# CONVEYOR-v2_0.net
KiCad netlist of a schematic drawn in EAGLE
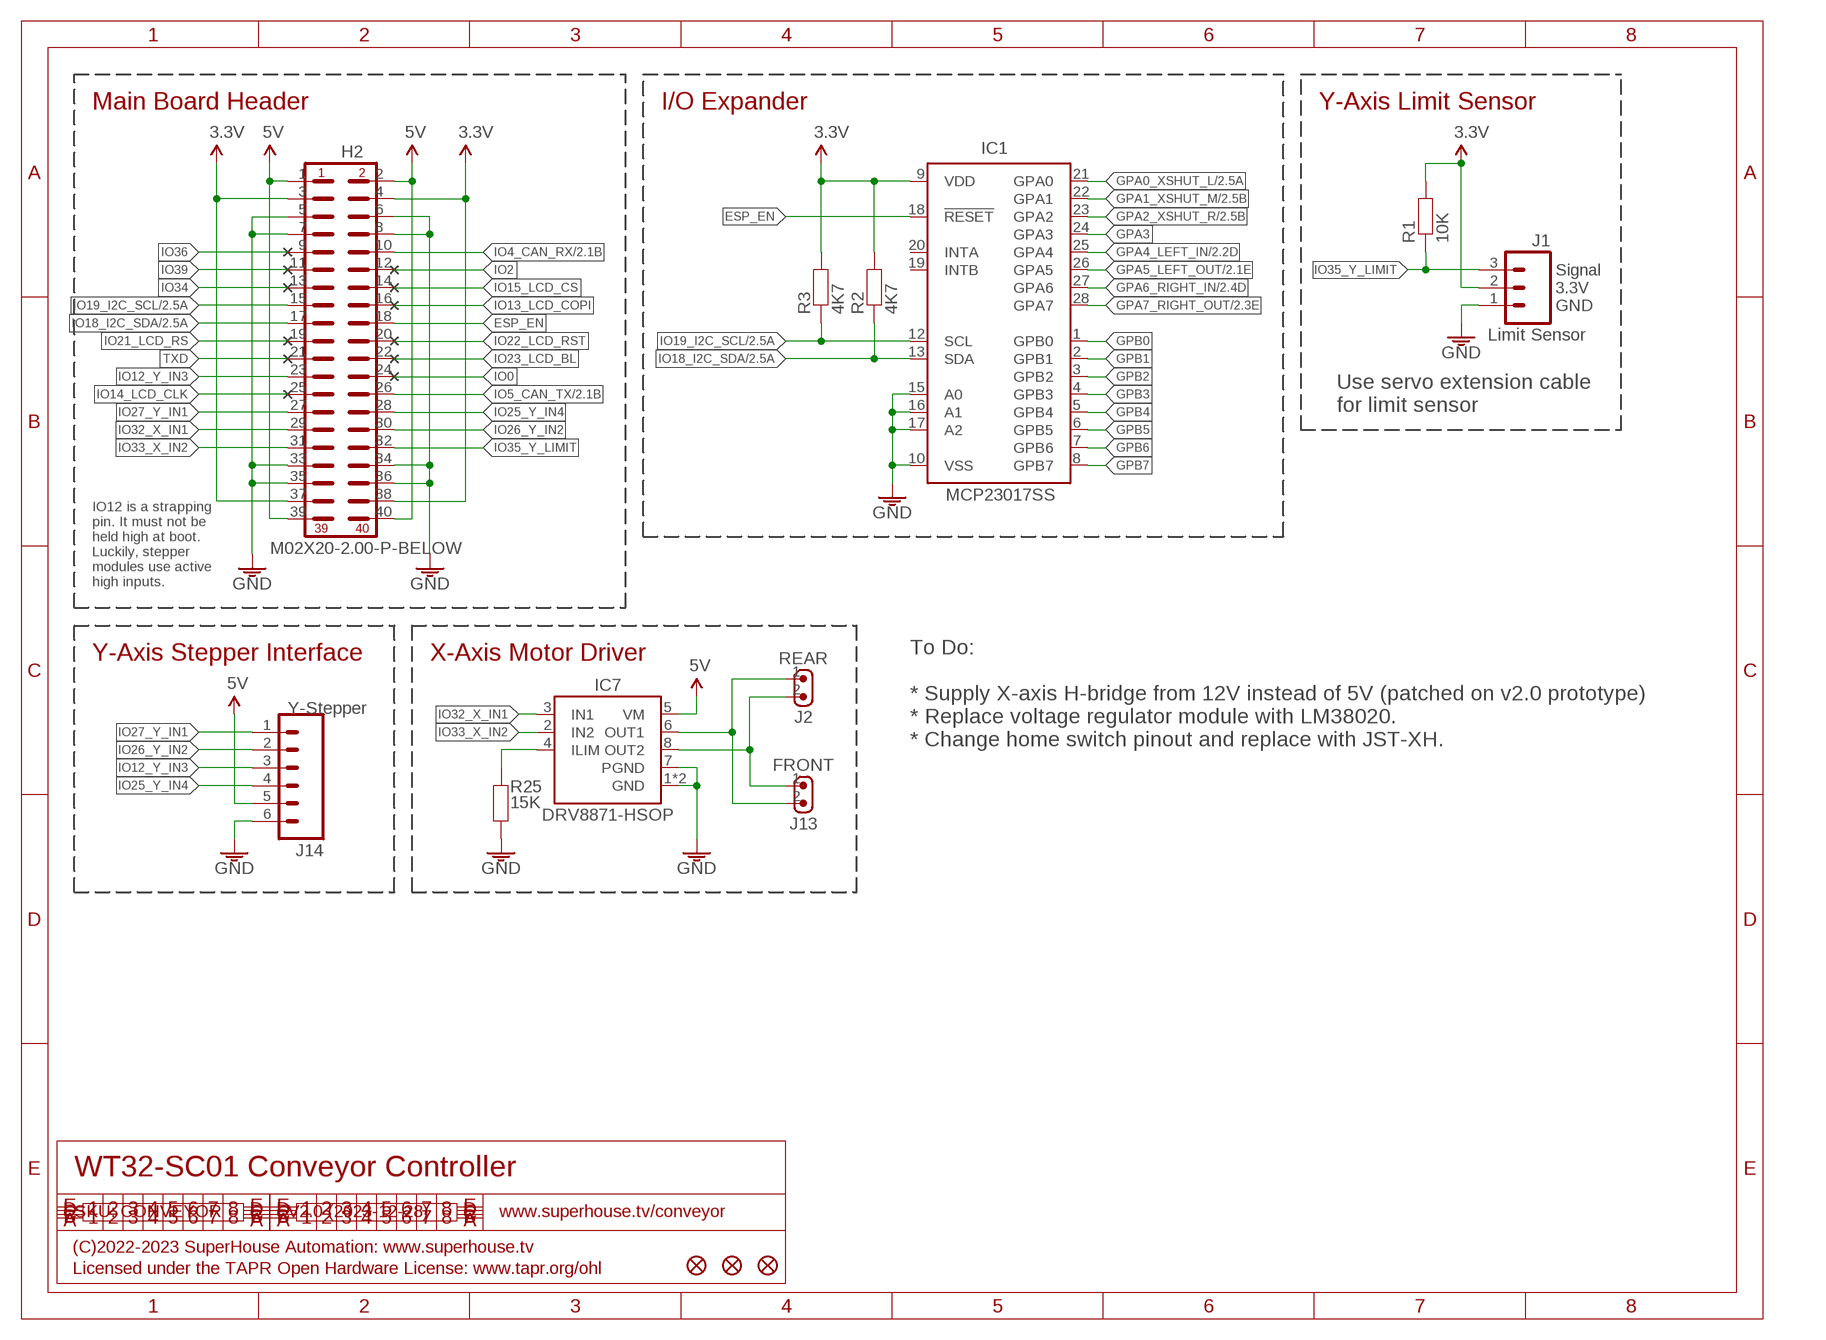
[diagram p0: schematic, sheet 1]
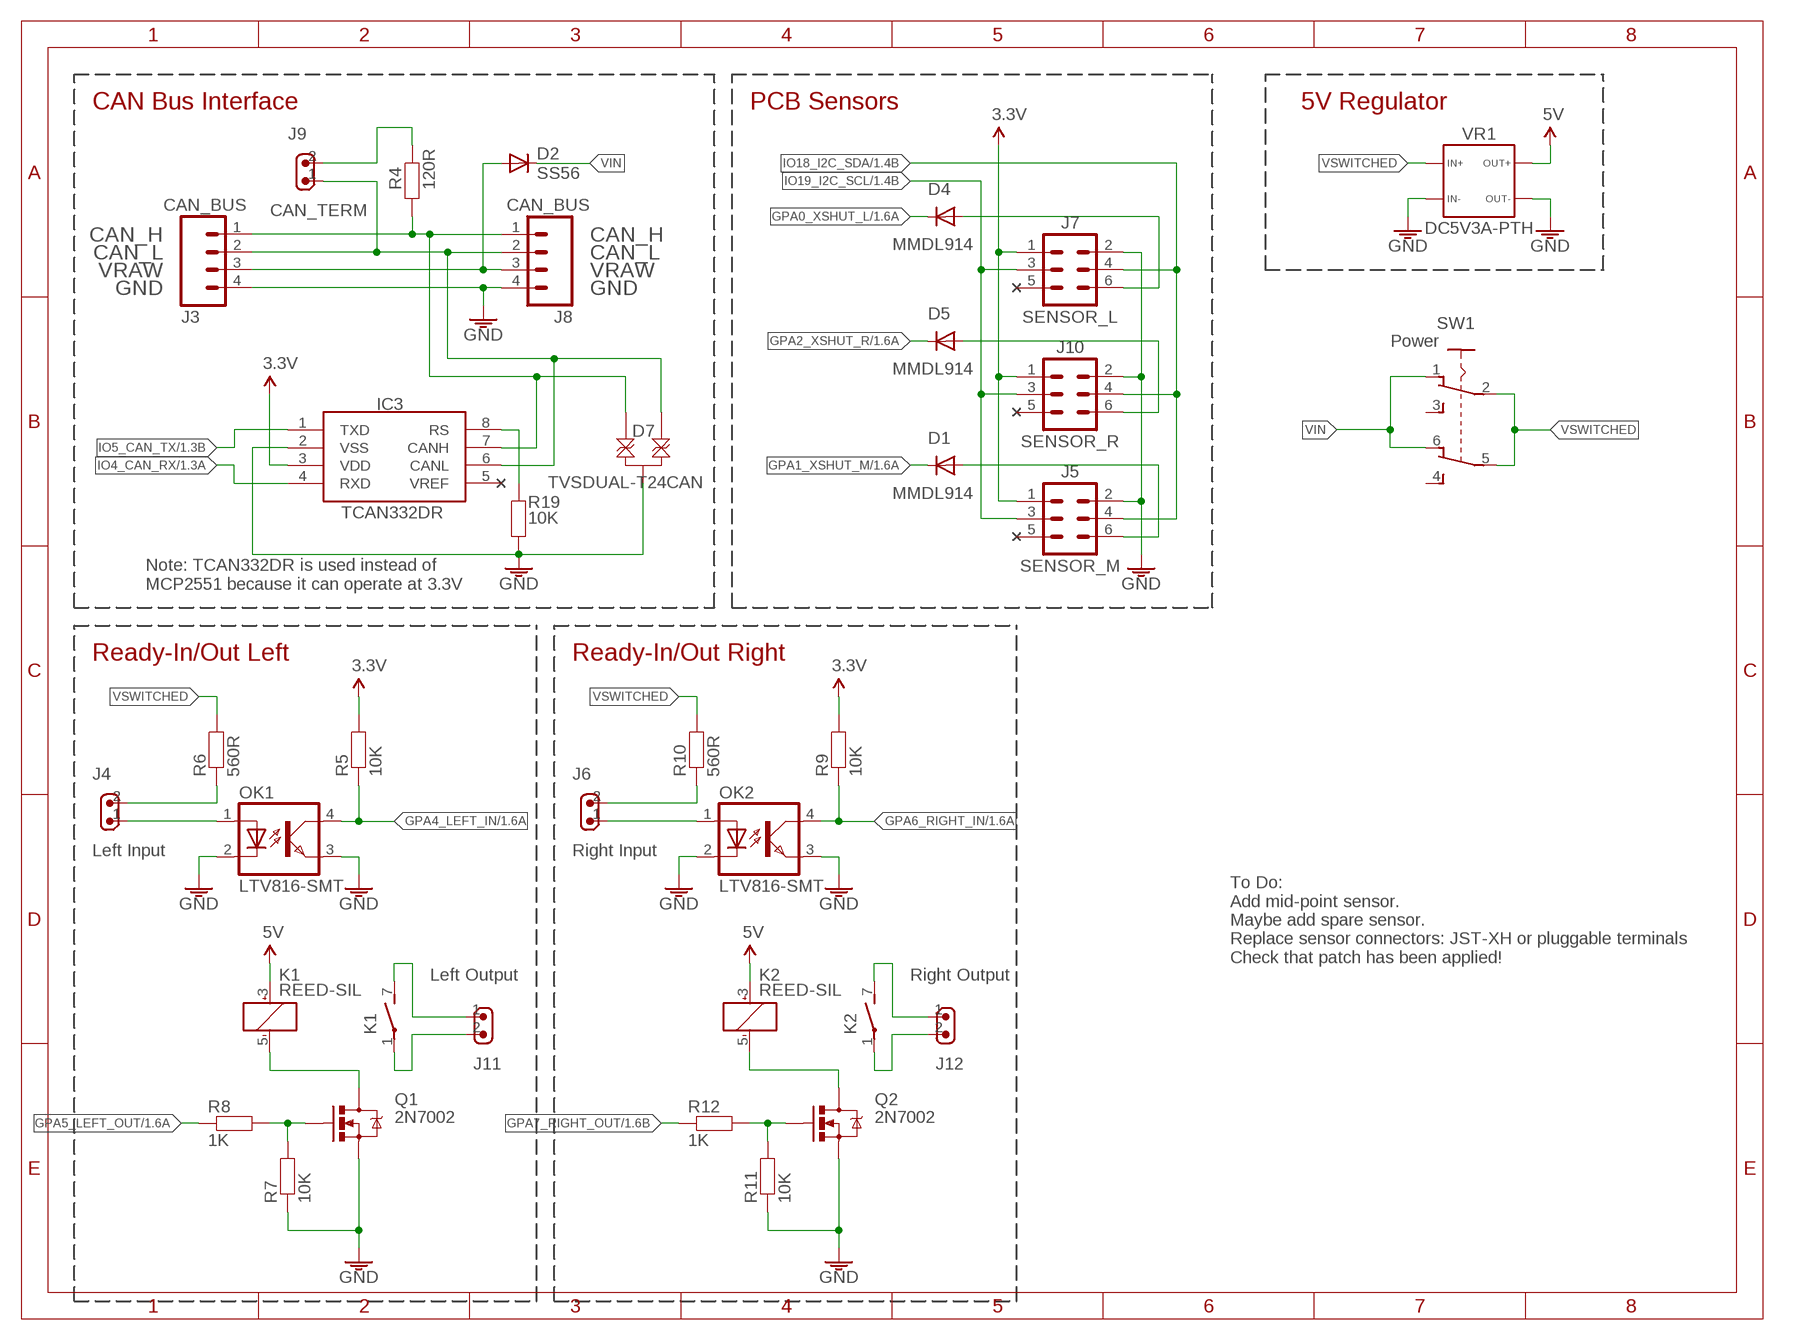
[diagram p1: schematic, sheet 2]

(export (version "E")
  (design (tool "Eeschema 10.0.6"))
  (components
    (comp (ref "D1")
      (value "MMDL914")
      (footprint "eagle-import:SOD-323")
      (libsource (lib "eagle-import") (part "DIODESOD"))
    )
    (comp (ref "D2")
      (value "SS56")
      (footprint "eagle-import:SMA-DIODE")
      (libsource (lib "eagle-import") (part "DIODESMA"))
    )
    (comp (ref "D4")
      (value "MMDL914")
      (footprint "eagle-import:SOD-323")
      (libsource (lib "eagle-import") (part "DIODESOD"))
    )
    (comp (ref "D5")
      (value "MMDL914")
      (footprint "eagle-import:SOD-323")
      (libsource (lib "eagle-import") (part "DIODESOD"))
    )
    (comp (ref "D7")
      (value "TVSDUAL-T24CAN")
      (footprint "eagle-import:SOT23-3")
      (libsource (lib "eagle-import") (part "TVSDUAL-T24CAN"))
    )
    (comp (ref "IC3")
      (value "TCAN332DR")
      (footprint "eagle-import:SO08")
      (libsource (lib "eagle-import") (part "MCP2551"))
    )
    (comp (ref "J3")
      (value "CAN_BUS")
      (footprint "eagle-import:SCREWTERMINAL-3.81MM-VERT-4")
      (libsource (lib "eagle-import") (part "M04-SCREW-3.81MM-VERT-PLUG"))
    )
    (comp (ref "J4")
      (value "Left Input")
      (footprint "eagle-import:1X02-KF2510")
      (libsource (lib "eagle-import") (part "M02-KF2510"))
    )
    (comp (ref "J5")
      (value "SENSOR_M")
      (footprint "eagle-import:2X3-2.54-SHROUDED")
      (libsource (lib "eagle-import") (part "M02X3-SHROUDED"))
    )
    (comp (ref "J6")
      (value "Right Input")
      (footprint "eagle-import:1X02-KF2510")
      (libsource (lib "eagle-import") (part "M02-KF2510"))
    )
    (comp (ref "J7")
      (value "SENSOR_L")
      (footprint "eagle-import:2X3-2.54-SHROUDED")
      (libsource (lib "eagle-import") (part "M02X3-SHROUDED"))
    )
    (comp (ref "J8")
      (value "CAN_BUS")
      (footprint "eagle-import:SCREWTERMINAL-3.81MM-VERT-4")
      (libsource (lib "eagle-import") (part "M04-SCREW-3.81MM-VERT-PLUG"))
    )
    (comp (ref "J9")
      (value "CAN_TERM")
      (footprint "eagle-import:1X02-P-JUMP-Y")
      (libsource (lib "eagle-import") (part "M02-PIN-JUMP-Y"))
    )
    (comp (ref "J10")
      (value "SENSOR_R")
      (footprint "eagle-import:2X3-2.54-SHROUDED")
      (libsource (lib "eagle-import") (part "M02X3-SHROUDED"))
    )
    (comp (ref "J11")
      (value "Left Output")
      (footprint "eagle-import:1X02-KF2510")
      (libsource (lib "eagle-import") (part "M02-KF2510"))
    )
    (comp (ref "J12")
      (value "Right Output")
      (footprint "eagle-import:1X02-KF2510")
      (libsource (lib "eagle-import") (part "M02-KF2510"))
    )
    (comp (ref "K1")
      (value "REED-SIL")
      (footprint "eagle-import:REED")
      (libsource (lib "eagle-import") (part "REED-SIL"))
    )
    (comp (ref "K2")
      (value "REED-SIL")
      (footprint "eagle-import:REED")
      (libsource (lib "eagle-import") (part "REED-SIL"))
    )
    (comp (ref "OK1")
      (value "LTV816-SMT")
      (footprint "eagle-import:SMD4")
      (libsource (lib "eagle-import") (part "LTV816-SMT"))
    )
    (comp (ref "OK2")
      (value "LTV816-SMT")
      (footprint "eagle-import:SMD4")
      (libsource (lib "eagle-import") (part "LTV816-SMT"))
    )
    (comp (ref "Q1")
      (value "2N7002")
      (footprint "eagle-import:SOT23-3")
      (libsource (lib "eagle-import") (part "MOSFET-NCHANNEL-233"))
    )
    (comp (ref "Q2")
      (value "2N7002")
      (footprint "eagle-import:SOT23-3")
      (libsource (lib "eagle-import") (part "MOSFET-NCHANNEL-233"))
    )
    (comp (ref "R4")
      (value "120R")
      (footprint "eagle-import:R2010")
      (libsource (lib "eagle-import") (part "RESISTOR2010"))
    )
    (comp (ref "R5")
      (value "10K")
      (footprint "eagle-import:R0603")
      (libsource (lib "eagle-import") (part "RESISTOR0603"))
    )
    (comp (ref "R6")
      (value "560R")
      (footprint "eagle-import:R0603")
      (libsource (lib "eagle-import") (part "RESISTOR0603"))
    )
    (comp (ref "R7")
      (value "10K")
      (footprint "eagle-import:R0603")
      (libsource (lib "eagle-import") (part "RESISTOR0603"))
    )
    (comp (ref "R8")
      (value "1K")
      (footprint "eagle-import:R0603")
      (libsource (lib "eagle-import") (part "RESISTOR0603"))
    )
    (comp (ref "R9")
      (value "10K")
      (footprint "eagle-import:R0603")
      (libsource (lib "eagle-import") (part "RESISTOR0603"))
    )
    (comp (ref "R10")
      (value "560R")
      (footprint "eagle-import:R0603")
      (libsource (lib "eagle-import") (part "RESISTOR0603"))
    )
    (comp (ref "R11")
      (value "10K")
      (footprint "eagle-import:R0603")
      (libsource (lib "eagle-import") (part "RESISTOR0603"))
    )
    (comp (ref "R12")
      (value "1K")
      (footprint "eagle-import:R0603")
      (libsource (lib "eagle-import") (part "RESISTOR0603"))
    )
    (comp (ref "R19")
      (value "10K")
      (footprint "eagle-import:R0603")
      (libsource (lib "eagle-import") (part "RESISTOR0603"))
    )
    (comp (ref "SW1")
      (value "Power")
      (footprint "eagle-import:7201SD9AV2BE")
      (libsource (lib "eagle-import") (part "SWITCH-DPDT3"))
    )
    (comp (ref "VR1")
      (value "DC5V3A-PTH")
      (footprint "eagle-import:DC5V3A-PTH")
      (libsource (lib "eagle-import") (part "DC5V3A-PTH"))
    )
    (comp (ref "H2")
      (value "M02X20-2.00-P-BELOW")
      (footprint "eagle-import:2X20-2.00-P-BELOW")
      (libsource (lib "eagle-import") (part "M02X20-2.00-P-BELOW"))
    )
    (comp (ref "IC1")
      (value "MCP23017SS")
      (footprint "eagle-import:SSOP28")
      (libsource (lib "eagle-import") (part "MCP23017SS"))
    )
    (comp (ref "IC7")
      (value "DRV8871-HSOP")
      (footprint "eagle-import:SOIC8T")
      (libsource (lib "eagle-import") (part "DRV8871-HSOP"))
    )
    (comp (ref "J1")
      (value "Limit Sensor")
      (footprint "eagle-import:1X03-P")
      (libsource (lib "eagle-import") (part "M03-PIN"))
    )
    (comp (ref "J2")
      (value "REAR")
      (footprint "eagle-import:JST-B2B-XH-A")
      (libsource (lib "eagle-import") (part "M02-B2B-XH"))
    )
    (comp (ref "J13")
      (value "FRONT")
      (footprint "eagle-import:JST-B2B-XH-A")
      (libsource (lib "eagle-import") (part "M02-B2B-XH"))
    )
    (comp (ref "J14")
      (value "Y-Stepper")
      (footprint "eagle-import:JST-B6B-XH-A")
      (libsource (lib "eagle-import") (part "M06-B6B-XH"))
    )
    (comp (ref "R1")
      (value "10K")
      (footprint "eagle-import:R0603")
      (libsource (lib "eagle-import") (part "RESISTOR0603"))
    )
    (comp (ref "R2")
      (value "4K7")
      (footprint "eagle-import:R0603")
      (libsource (lib "eagle-import") (part "RESISTOR0603"))
    )
    (comp (ref "R3")
      (value "4K7")
      (footprint "eagle-import:R0603")
      (libsource (lib "eagle-import") (part "RESISTOR0603"))
    )
    (comp (ref "R25")
      (value "15K")
      (footprint "eagle-import:R0603")
      (libsource (lib "eagle-import") (part "RESISTOR0603"))
    )
    (comp (ref "U$4")
      (value "FIDUCIAL1X2.5")
      (footprint "eagle-import:FIDUCIAL-1X2.5")
      (libsource (lib "eagle-import") (part "FIDUCIAL1X2.5"))
    )
    (comp (ref "U$5")
      (value "FIDUCIAL1X2.5")
      (footprint "eagle-import:FIDUCIAL-1X2.5")
      (libsource (lib "eagle-import") (part "FIDUCIAL1X2.5"))
    )
    (comp (ref "U$6")
      (value "FIDUCIAL1X2.5")
      (footprint "eagle-import:FIDUCIAL-1X2.5")
      (libsource (lib "eagle-import") (part "FIDUCIAL1X2.5"))
    )
  )
  (nets
    (net (code "1") (name "3.3V") (class "Default")
      (node (ref "H2") (pin "3") (pinfunction "3_3") (pintype "passive"))
      (node (ref "H2") (pin "37") (pinfunction "37_37") (pintype "passive"))
      (node (ref "H2") (pin "38") (pinfunction "38_38") (pintype "passive"))
      (node (ref "H2") (pin "4") (pinfunction "4_4") (pintype "passive"))
      (node (ref "IC1") (pin "9") (pinfunction "VDD_9") (pintype "power_in"))
      (node (ref "IC3") (pin "3") (pinfunction "VDD_3") (pintype "bidirectional"))
      (node (ref "J1") (pin "2") (pinfunction "2_2") (pintype "passive"))
      (node (ref "J10") (pin "1") (pinfunction "1_1") (pintype "passive"))
      (node (ref "J5") (pin "1") (pinfunction "1_1") (pintype "passive"))
      (node (ref "J7") (pin "1") (pinfunction "1_1") (pintype "passive"))
      (node (ref "R1") (pin "2") (pinfunction "2_2") (pintype "passive"))
      (node (ref "R2") (pin "2") (pinfunction "2_2") (pintype "passive"))
      (node (ref "R3") (pin "2") (pinfunction "2_2") (pintype "passive"))
      (node (ref "R5") (pin "2") (pinfunction "2_2") (pintype "passive"))
      (node (ref "R9") (pin "2") (pinfunction "2_2") (pintype "passive"))
    )
    (net (code "2") (name "5V") (class "Default")
      (node (ref "H2") (pin "1") (pinfunction "1_1") (pintype "passive"))
      (node (ref "H2") (pin "2") (pinfunction "2_2") (pintype "passive"))
      (node (ref "H2") (pin "39") (pinfunction "39_39") (pintype "passive"))
      (node (ref "H2") (pin "40") (pinfunction "40_40") (pintype "passive"))
      (node (ref "IC7") (pin "5") (pinfunction "VM_5") (pintype "passive"))
      (node (ref "J14") (pin "5") (pinfunction "5_5") (pintype "passive"))
      (node (ref "K1") (pin "3") (pinfunction "+_3") (pintype "passive"))
      (node (ref "K2") (pin "3") (pinfunction "+_3") (pintype "passive"))
      (node (ref "VR1") (pin "3A") (pinfunction "3_3A") (pintype "bidirectional"))
      (node (ref "VR1") (pin "3B") (pinfunction "3_3B") (pintype "bidirectional"))
    )
    (net (code "3") (name "ESP_EN") (class "Default")
      (node (ref "H2") (pin "18") (pinfunction "18_18") (pintype "passive"))
      (node (ref "IC1") (pin "18") (pinfunction "~{RESET}_18") (pintype "input"))
    )
    (net (code "4") (name "GND") (class "Default")
      (node (ref "D7") (pin "3") (pinfunction "3_3") (pintype "passive"))
      (node (ref "H2") (pin "33") (pinfunction "33_33") (pintype "passive"))
      (node (ref "H2") (pin "34") (pinfunction "34_34") (pintype "passive"))
      (node (ref "H2") (pin "35") (pinfunction "35_35") (pintype "passive"))
      (node (ref "H2") (pin "36") (pinfunction "36_36") (pintype "passive"))
      (node (ref "H2") (pin "5") (pinfunction "5_5") (pintype "passive"))
      (node (ref "H2") (pin "6") (pinfunction "6_6") (pintype "passive"))
      (node (ref "H2") (pin "7") (pinfunction "7_7") (pintype "passive"))
      (node (ref "H2") (pin "8") (pinfunction "8_8") (pintype "passive"))
      (node (ref "IC1") (pin "10") (pinfunction "VSS_10") (pintype "power_in"))
      (node (ref "IC1") (pin "15") (pinfunction "A0_15") (pintype "input"))
      (node (ref "IC1") (pin "16") (pinfunction "A1_16") (pintype "input"))
      (node (ref "IC1") (pin "17") (pinfunction "A2_17") (pintype "input"))
      (node (ref "IC3") (pin "2") (pinfunction "VSS_2") (pintype "bidirectional"))
      (node (ref "IC7") (pin "1") (pinfunction "GND_1") (pintype "power_in"))
      (node (ref "IC7") (pin "7") (pinfunction "PGND_7") (pintype "power_in"))
      (node (ref "IC7") (pin "TGND") (pinfunction "GND_TGND") (pintype "power_in"))
      (node (ref "J1") (pin "1") (pinfunction "1_1") (pintype "passive"))
      (node (ref "J10") (pin "2") (pinfunction "2_2") (pintype "passive"))
      (node (ref "J14") (pin "6") (pinfunction "6_6") (pintype "passive"))
      (node (ref "J3") (pin "4") (pinfunction "4_4") (pintype "passive"))
      (node (ref "J5") (pin "2") (pinfunction "2_2") (pintype "passive"))
      (node (ref "J7") (pin "2") (pinfunction "2_2") (pintype "passive"))
      (node (ref "J8") (pin "4") (pinfunction "4_4") (pintype "passive"))
      (node (ref "OK1") (pin "2") (pinfunction "C_2") (pintype "passive"))
      (node (ref "OK1") (pin "3") (pinfunction "EMIT_3") (pintype "passive"))
      (node (ref "OK2") (pin "2") (pinfunction "C_2") (pintype "passive"))
      (node (ref "OK2") (pin "3") (pinfunction "EMIT_3") (pintype "passive"))
      (node (ref "Q1") (pin "2") (pinfunction "S_2") (pintype "passive"))
      (node (ref "Q2") (pin "2") (pinfunction "S_2") (pintype "passive"))
      (node (ref "R11") (pin "1") (pinfunction "1_1") (pintype "passive"))
      (node (ref "R19") (pin "1") (pinfunction "1_1") (pintype "passive"))
      (node (ref "R25") (pin "1") (pinfunction "1_1") (pintype "passive"))
      (node (ref "R7") (pin "1") (pinfunction "1_1") (pintype "passive"))
      (node (ref "VR1") (pin "1A") (pinfunction "1_1A") (pintype "bidirectional"))
      (node (ref "VR1") (pin "1B") (pinfunction "1_1B") (pintype "bidirectional"))
      (node (ref "VR1") (pin "4A") (pinfunction "4_4A") (pintype "bidirectional"))
      (node (ref "VR1") (pin "4B") (pinfunction "4_4B") (pintype "bidirectional"))
    )
    (net (code "5") (name "GPA0_XSHUT_L") (class "Default")
      (node (ref "D4") (pin "1") (pinfunction "C_1") (pintype "passive"))
      (node (ref "IC1") (pin "21") (pinfunction "GPA0_21") (pintype "bidirectional"))
    )
    (net (code "6") (name "GPA1_XSHUT_M") (class "Default")
      (node (ref "D1") (pin "1") (pinfunction "C_1") (pintype "passive"))
      (node (ref "IC1") (pin "22") (pinfunction "GPA1_22") (pintype "bidirectional"))
    )
    (net (code "7") (name "GPA2_XSHUT_R") (class "Default")
      (node (ref "D5") (pin "1") (pinfunction "C_1") (pintype "passive"))
      (node (ref "IC1") (pin "23") (pinfunction "GPA2_23") (pintype "bidirectional"))
    )
    (net (code "8") (name "GPA3") (class "Default")
      (node (ref "IC1") (pin "24") (pinfunction "GPA3_24") (pintype "bidirectional"))
    )
    (net (code "9") (name "GPA4_LEFT_IN") (class "Default")
      (node (ref "IC1") (pin "25") (pinfunction "GPA4_25") (pintype "bidirectional"))
      (node (ref "OK1") (pin "4") (pinfunction "COL_4") (pintype "passive"))
      (node (ref "R5") (pin "1") (pinfunction "1_1") (pintype "passive"))
    )
    (net (code "10") (name "GPA5_LEFT_OUT") (class "Default")
      (node (ref "IC1") (pin "26") (pinfunction "GPA5_26") (pintype "bidirectional"))
      (node (ref "R8") (pin "1") (pinfunction "1_1") (pintype "passive"))
    )
    (net (code "11") (name "GPA6_RIGHT_IN") (class "Default")
      (node (ref "IC1") (pin "27") (pinfunction "GPA6_27") (pintype "bidirectional"))
      (node (ref "OK2") (pin "4") (pinfunction "COL_4") (pintype "passive"))
      (node (ref "R9") (pin "1") (pinfunction "1_1") (pintype "passive"))
    )
    (net (code "12") (name "GPA7_RIGHT_OUT") (class "Default")
      (node (ref "IC1") (pin "28") (pinfunction "GPA7_28") (pintype "bidirectional"))
      (node (ref "R12") (pin "1") (pinfunction "1_1") (pintype "passive"))
    )
    (net (code "13") (name "GPB0") (class "Default")
      (node (ref "IC1") (pin "1") (pinfunction "GPB0_1") (pintype "bidirectional"))
    )
    (net (code "14") (name "GPB1") (class "Default")
      (node (ref "IC1") (pin "2") (pinfunction "GPB1_2") (pintype "bidirectional"))
    )
    (net (code "15") (name "GPB2") (class "Default")
      (node (ref "IC1") (pin "3") (pinfunction "GPB2_3") (pintype "bidirectional"))
    )
    (net (code "16") (name "GPB3") (class "Default")
      (node (ref "IC1") (pin "4") (pinfunction "GPB3_4") (pintype "bidirectional"))
    )
    (net (code "17") (name "GPB4") (class "Default")
      (node (ref "IC1") (pin "5") (pinfunction "GPB4_5") (pintype "bidirectional"))
    )
    (net (code "18") (name "GPB5") (class "Default")
      (node (ref "IC1") (pin "6") (pinfunction "GPB5_6") (pintype "bidirectional"))
    )
    (net (code "19") (name "GPB6") (class "Default")
      (node (ref "IC1") (pin "7") (pinfunction "GPB6_7") (pintype "bidirectional"))
    )
    (net (code "20") (name "GPB7") (class "Default")
      (node (ref "IC1") (pin "8") (pinfunction "GPB7_8") (pintype "bidirectional"))
    )
    (net (code "21") (name "IO0") (class "Default")
      (node (ref "H2") (pin "24") (pinfunction "24_24") (pintype "passive"))
    )
    (net (code "22") (name "IO2") (class "Default")
      (node (ref "H2") (pin "12") (pinfunction "12_12") (pintype "passive"))
    )
    (net (code "23") (name "IO4_CAN_RX") (class "Default")
      (node (ref "H2") (pin "10") (pinfunction "10_10") (pintype "passive"))
      (node (ref "IC3") (pin "4") (pinfunction "RXD_4") (pintype "bidirectional"))
    )
    (net (code "24") (name "IO5_CAN_TX") (class "Default")
      (node (ref "H2") (pin "26") (pinfunction "26_26") (pintype "passive"))
      (node (ref "IC3") (pin "1") (pinfunction "TXD_1") (pintype "bidirectional"))
    )
    (net (code "25") (name "IO12_Y_IN3") (class "Default")
      (node (ref "H2") (pin "23") (pinfunction "23_23") (pintype "passive"))
      (node (ref "J14") (pin "3") (pinfunction "3_3") (pintype "passive"))
    )
    (net (code "26") (name "IO13_LCD_COPI") (class "Default")
      (node (ref "H2") (pin "16") (pinfunction "16_16") (pintype "passive"))
    )
    (net (code "27") (name "IO14_LCD_CLK") (class "Default")
      (node (ref "H2") (pin "25") (pinfunction "25_25") (pintype "passive"))
    )
    (net (code "28") (name "IO15_LCD_CS") (class "Default")
      (node (ref "H2") (pin "14") (pinfunction "14_14") (pintype "passive"))
    )
    (net (code "29") (name "IO18_I2C_SDA") (class "Default")
      (node (ref "H2") (pin "17") (pinfunction "17_17") (pintype "passive"))
      (node (ref "IC1") (pin "13") (pinfunction "SDA_13") (pintype "bidirectional"))
      (node (ref "J10") (pin "4") (pinfunction "4_4") (pintype "passive"))
      (node (ref "J5") (pin "4") (pinfunction "4_4") (pintype "passive"))
      (node (ref "J7") (pin "4") (pinfunction "4_4") (pintype "passive"))
      (node (ref "R2") (pin "1") (pinfunction "1_1") (pintype "passive"))
    )
    (net (code "30") (name "IO19_I2C_SCL") (class "Default")
      (node (ref "H2") (pin "15") (pinfunction "15_15") (pintype "passive"))
      (node (ref "IC1") (pin "12") (pinfunction "SCL_12") (pintype "input"))
      (node (ref "J10") (pin "3") (pinfunction "3_3") (pintype "passive"))
      (node (ref "J5") (pin "3") (pinfunction "3_3") (pintype "passive"))
      (node (ref "J7") (pin "3") (pinfunction "3_3") (pintype "passive"))
      (node (ref "R3") (pin "1") (pinfunction "1_1") (pintype "passive"))
    )
    (net (code "31") (name "IO21_LCD_RS") (class "Default")
      (node (ref "H2") (pin "19") (pinfunction "19_19") (pintype "passive"))
    )
    (net (code "32") (name "IO22_LCD_RST") (class "Default")
      (node (ref "H2") (pin "20") (pinfunction "20_20") (pintype "passive"))
    )
    (net (code "33") (name "IO23_LCD_BL") (class "Default")
      (node (ref "H2") (pin "22") (pinfunction "22_22") (pintype "passive"))
    )
    (net (code "34") (name "IO25_Y_IN4") (class "Default")
      (node (ref "H2") (pin "28") (pinfunction "28_28") (pintype "passive"))
      (node (ref "J14") (pin "4") (pinfunction "4_4") (pintype "passive"))
    )
    (net (code "35") (name "IO26_Y_IN2") (class "Default")
      (node (ref "H2") (pin "30") (pinfunction "30_30") (pintype "passive"))
      (node (ref "J14") (pin "2") (pinfunction "2_2") (pintype "passive"))
    )
    (net (code "36") (name "IO27_Y_IN1") (class "Default")
      (node (ref "H2") (pin "27") (pinfunction "27_27") (pintype "passive"))
      (node (ref "J14") (pin "1") (pinfunction "1_1") (pintype "passive"))
    )
    (net (code "37") (name "IO32_X_IN1") (class "Default")
      (node (ref "H2") (pin "29") (pinfunction "29_29") (pintype "passive"))
      (node (ref "IC7") (pin "3") (pinfunction "IN1_3") (pintype "input"))
    )
    (net (code "38") (name "IO33_X_IN2") (class "Default")
      (node (ref "H2") (pin "31") (pinfunction "31_31") (pintype "passive"))
      (node (ref "IC7") (pin "2") (pinfunction "IN2_2") (pintype "input"))
    )
    (net (code "39") (name "IO34") (class "Default")
      (node (ref "H2") (pin "13") (pinfunction "13_13") (pintype "passive"))
    )
    (net (code "40") (name "IO35_Y_LIMIT") (class "Default")
      (node (ref "H2") (pin "32") (pinfunction "32_32") (pintype "passive"))
      (node (ref "J1") (pin "3") (pinfunction "3_3") (pintype "passive"))
      (node (ref "R1") (pin "1") (pinfunction "1_1") (pintype "passive"))
    )
    (net (code "41") (name "IO36") (class "Default")
      (node (ref "H2") (pin "9") (pinfunction "9_9") (pintype "passive"))
    )
    (net (code "42") (name "IO39") (class "Default")
      (node (ref "H2") (pin "11") (pinfunction "11_11") (pintype "passive"))
    )
    (net (code "43") (name "Net-(D1-A)") (class "Default")
      (node (ref "D1") (pin "2") (pinfunction "A_2") (pintype "passive"))
      (node (ref "J5") (pin "6") (pinfunction "6_6") (pintype "passive"))
    )
    (net (code "44") (name "Net-(D2-PadA)") (class "Default")
      (node (ref "D2") (pin "A") (pinfunction "A_A") (pintype "passive"))
      (node (ref "J3") (pin "3") (pinfunction "3_3") (pintype "passive"))
      (node (ref "J8") (pin "3") (pinfunction "3_3") (pintype "passive"))
    )
    (net (code "45") (name "Net-(D4-A)") (class "Default")
      (node (ref "D4") (pin "2") (pinfunction "A_2") (pintype "passive"))
      (node (ref "J7") (pin "6") (pinfunction "6_6") (pintype "passive"))
    )
    (net (code "46") (name "Net-(D5-A)") (class "Default")
      (node (ref "D5") (pin "2") (pinfunction "A_2") (pintype "passive"))
      (node (ref "J10") (pin "6") (pinfunction "6_6") (pintype "passive"))
    )
    (net (code "47") (name "Net-(IC3-CANH)") (class "Default")
      (node (ref "D7") (pin "2") (pinfunction "2_2") (pintype "passive"))
      (node (ref "IC3") (pin "7") (pinfunction "CANH_7") (pintype "bidirectional"))
      (node (ref "J3") (pin "1") (pinfunction "1_1") (pintype "passive"))
      (node (ref "J8") (pin "1") (pinfunction "1_1") (pintype "passive"))
      (node (ref "R4") (pin "1") (pinfunction "1_1") (pintype "passive"))
    )
    (net (code "48") (name "Net-(IC3-CANL)") (class "Default")
      (node (ref "D7") (pin "1") (pinfunction "1_1") (pintype "passive"))
      (node (ref "IC3") (pin "6") (pinfunction "CANL_6") (pintype "bidirectional"))
      (node (ref "J3") (pin "2") (pinfunction "2_2") (pintype "passive"))
      (node (ref "J8") (pin "2") (pinfunction "2_2") (pintype "passive"))
      (node (ref "J9") (pin "1") (pinfunction "1_1") (pintype "passive"))
    )
    (net (code "49") (name "Net-(IC3-RS)") (class "Default")
      (node (ref "IC3") (pin "8") (pinfunction "RS_8") (pintype "bidirectional"))
      (node (ref "R19") (pin "2") (pinfunction "2_2") (pintype "passive"))
    )
    (net (code "50") (name "Net-(IC7-ILIM)") (class "Default")
      (node (ref "IC7") (pin "4") (pinfunction "ILIM_4") (pintype "bidirectional"))
      (node (ref "R25") (pin "2") (pinfunction "2_2") (pintype "passive"))
    )
    (net (code "51") (name "Net-(IC7-OUT1)") (class "Default")
      (node (ref "IC7") (pin "6") (pinfunction "OUT1_6") (pintype "output"))
      (node (ref "J13") (pin "2") (pinfunction "2_2") (pintype "passive"))
      (node (ref "J2") (pin "1") (pinfunction "1_1") (pintype "passive"))
    )
    (net (code "52") (name "Net-(IC7-OUT2)") (class "Default")
      (node (ref "IC7") (pin "8") (pinfunction "OUT2_8") (pintype "output"))
      (node (ref "J13") (pin "1") (pinfunction "1_1") (pintype "passive"))
      (node (ref "J2") (pin "2") (pinfunction "2_2") (pintype "passive"))
    )
    (net (code "53") (name "Net-(J4-Pad2)") (class "Default")
      (node (ref "J4") (pin "2") (pinfunction "2_2") (pintype "passive"))
      (node (ref "R6") (pin "1") (pinfunction "1_1") (pintype "passive"))
    )
    (net (code "54") (name "Net-(J6-Pad2)") (class "Default")
      (node (ref "J6") (pin "2") (pinfunction "2_2") (pintype "passive"))
      (node (ref "R10") (pin "1") (pinfunction "1_1") (pintype "passive"))
    )
    (net (code "55") (name "Net-(J9-Pad2)") (class "Default")
      (node (ref "J9") (pin "2") (pinfunction "2_2") (pintype "passive"))
      (node (ref "R4") (pin "2") (pinfunction "2_2") (pintype "passive"))
    )
    (net (code "56") (name "Net-(K1A--)") (class "Default")
      (node (ref "K1") (pin "5") (pinfunction "-_5") (pintype "passive"))
      (node (ref "Q1") (pin "3") (pinfunction "D_3") (pintype "passive"))
    )
    (net (code "57") (name "Net-(K1B-P)") (class "Default")
      (node (ref "J11") (pin "2") (pinfunction "2_2") (pintype "passive"))
      (node (ref "K1") (pin "1") (pinfunction "P_1") (pintype "passive"))
    )
    (net (code "58") (name "Net-(K1B-S)") (class "Default")
      (node (ref "J11") (pin "1") (pinfunction "1_1") (pintype "passive"))
      (node (ref "K1") (pin "7") (pinfunction "S_7") (pintype "passive"))
    )
    (net (code "59") (name "Net-(K2A--)") (class "Default")
      (node (ref "K2") (pin "5") (pinfunction "-_5") (pintype "passive"))
      (node (ref "Q2") (pin "3") (pinfunction "D_3") (pintype "passive"))
    )
    (net (code "60") (name "Net-(K2B-P)") (class "Default")
      (node (ref "J12") (pin "2") (pinfunction "2_2") (pintype "passive"))
      (node (ref "K2") (pin "1") (pinfunction "P_1") (pintype "passive"))
    )
    (net (code "61") (name "Net-(K2B-S)") (class "Default")
      (node (ref "J12") (pin "1") (pinfunction "1_1") (pintype "passive"))
      (node (ref "K2") (pin "7") (pinfunction "S_7") (pintype "passive"))
    )
    (net (code "62") (name "Net-(OK1-A)") (class "Default")
      (node (ref "J4") (pin "1") (pinfunction "1_1") (pintype "passive"))
      (node (ref "OK1") (pin "1") (pinfunction "A_1") (pintype "passive"))
    )
    (net (code "63") (name "Net-(OK2-A)") (class "Default")
      (node (ref "J6") (pin "1") (pinfunction "1_1") (pintype "passive"))
      (node (ref "OK2") (pin "1") (pinfunction "A_1") (pintype "passive"))
    )
    (net (code "64") (name "Net-(Q1-G)") (class "Default")
      (node (ref "Q1") (pin "1") (pinfunction "G_1") (pintype "passive"))
      (node (ref "R7") (pin "2") (pinfunction "2_2") (pintype "passive"))
      (node (ref "R8") (pin "2") (pinfunction "2_2") (pintype "passive"))
    )
    (net (code "65") (name "Net-(Q2-G)") (class "Default")
      (node (ref "Q2") (pin "1") (pinfunction "G_1") (pintype "passive"))
      (node (ref "R11") (pin "2") (pinfunction "2_2") (pintype "passive"))
      (node (ref "R12") (pin "2") (pinfunction "2_2") (pintype "passive"))
    )
    (net (code "66") (name "TXD") (class "Default")
      (node (ref "H2") (pin "21") (pinfunction "21_21") (pintype "passive"))
    )
    (net (code "67") (name "VIN") (class "Default")
      (node (ref "D2") (pin "C") (pinfunction "C_C") (pintype "passive"))
      (node (ref "SW1") (pin "1") (pinfunction "1_1") (pintype "passive"))
      (node (ref "SW1") (pin "6") (pinfunction "6_6") (pintype "passive"))
    )
    (net (code "68") (name "VSWITCHED") (class "Default")
      (node (ref "R10") (pin "2") (pinfunction "2_2") (pintype "passive"))
      (node (ref "R6") (pin "2") (pinfunction "2_2") (pintype "passive"))
      (node (ref "SW1") (pin "2") (pinfunction "2_2") (pintype "passive"))
      (node (ref "SW1") (pin "5") (pinfunction "5_5") (pintype "passive"))
      (node (ref "VR1") (pin "2A") (pinfunction "2_2A") (pintype "bidirectional"))
      (node (ref "VR1") (pin "2B") (pinfunction "2_2B") (pintype "bidirectional"))
    )
    (net (code "69") (name "unconnected-(IC1-INTA-Pad20)") (class "Default")
      (node (ref "IC1") (pin "20") (pinfunction "INTA_20") (pintype "output"))
    )
    (net (code "70") (name "unconnected-(IC1-INTB-Pad19)") (class "Default")
      (node (ref "IC1") (pin "19") (pinfunction "INTB_19") (pintype "output"))
    )
    (net (code "71") (name "unconnected-(IC3-VREF-Pad5)") (class "Default")
      (node (ref "IC3") (pin "5") (pinfunction "VREF_5") (pintype "bidirectional"))
    )
    (net (code "72") (name "unconnected-(J5-Pad5)") (class "Default")
      (node (ref "J5") (pin "5") (pinfunction "5_5") (pintype "passive"))
    )
    (net (code "73") (name "unconnected-(J7-Pad5)") (class "Default")
      (node (ref "J7") (pin "5") (pinfunction "5_5") (pintype "passive"))
    )
    (net (code "74") (name "unconnected-(J10-Pad5)") (class "Default")
      (node (ref "J10") (pin "5") (pinfunction "5_5") (pintype "passive"))
    )
    (net (code "75") (name "unconnected-(SW1-Pad3)") (class "Default")
      (node (ref "SW1") (pin "3") (pinfunction "3_3") (pintype "passive"))
    )
    (net (code "76") (name "unconnected-(SW1-Pad4)") (class "Default")
      (node (ref "SW1") (pin "4") (pinfunction "4_4") (pintype "passive"))
    )
  )
)
